# Supply_Modulator.net
KiCad netlist of a schematic drawn in Altium Designer
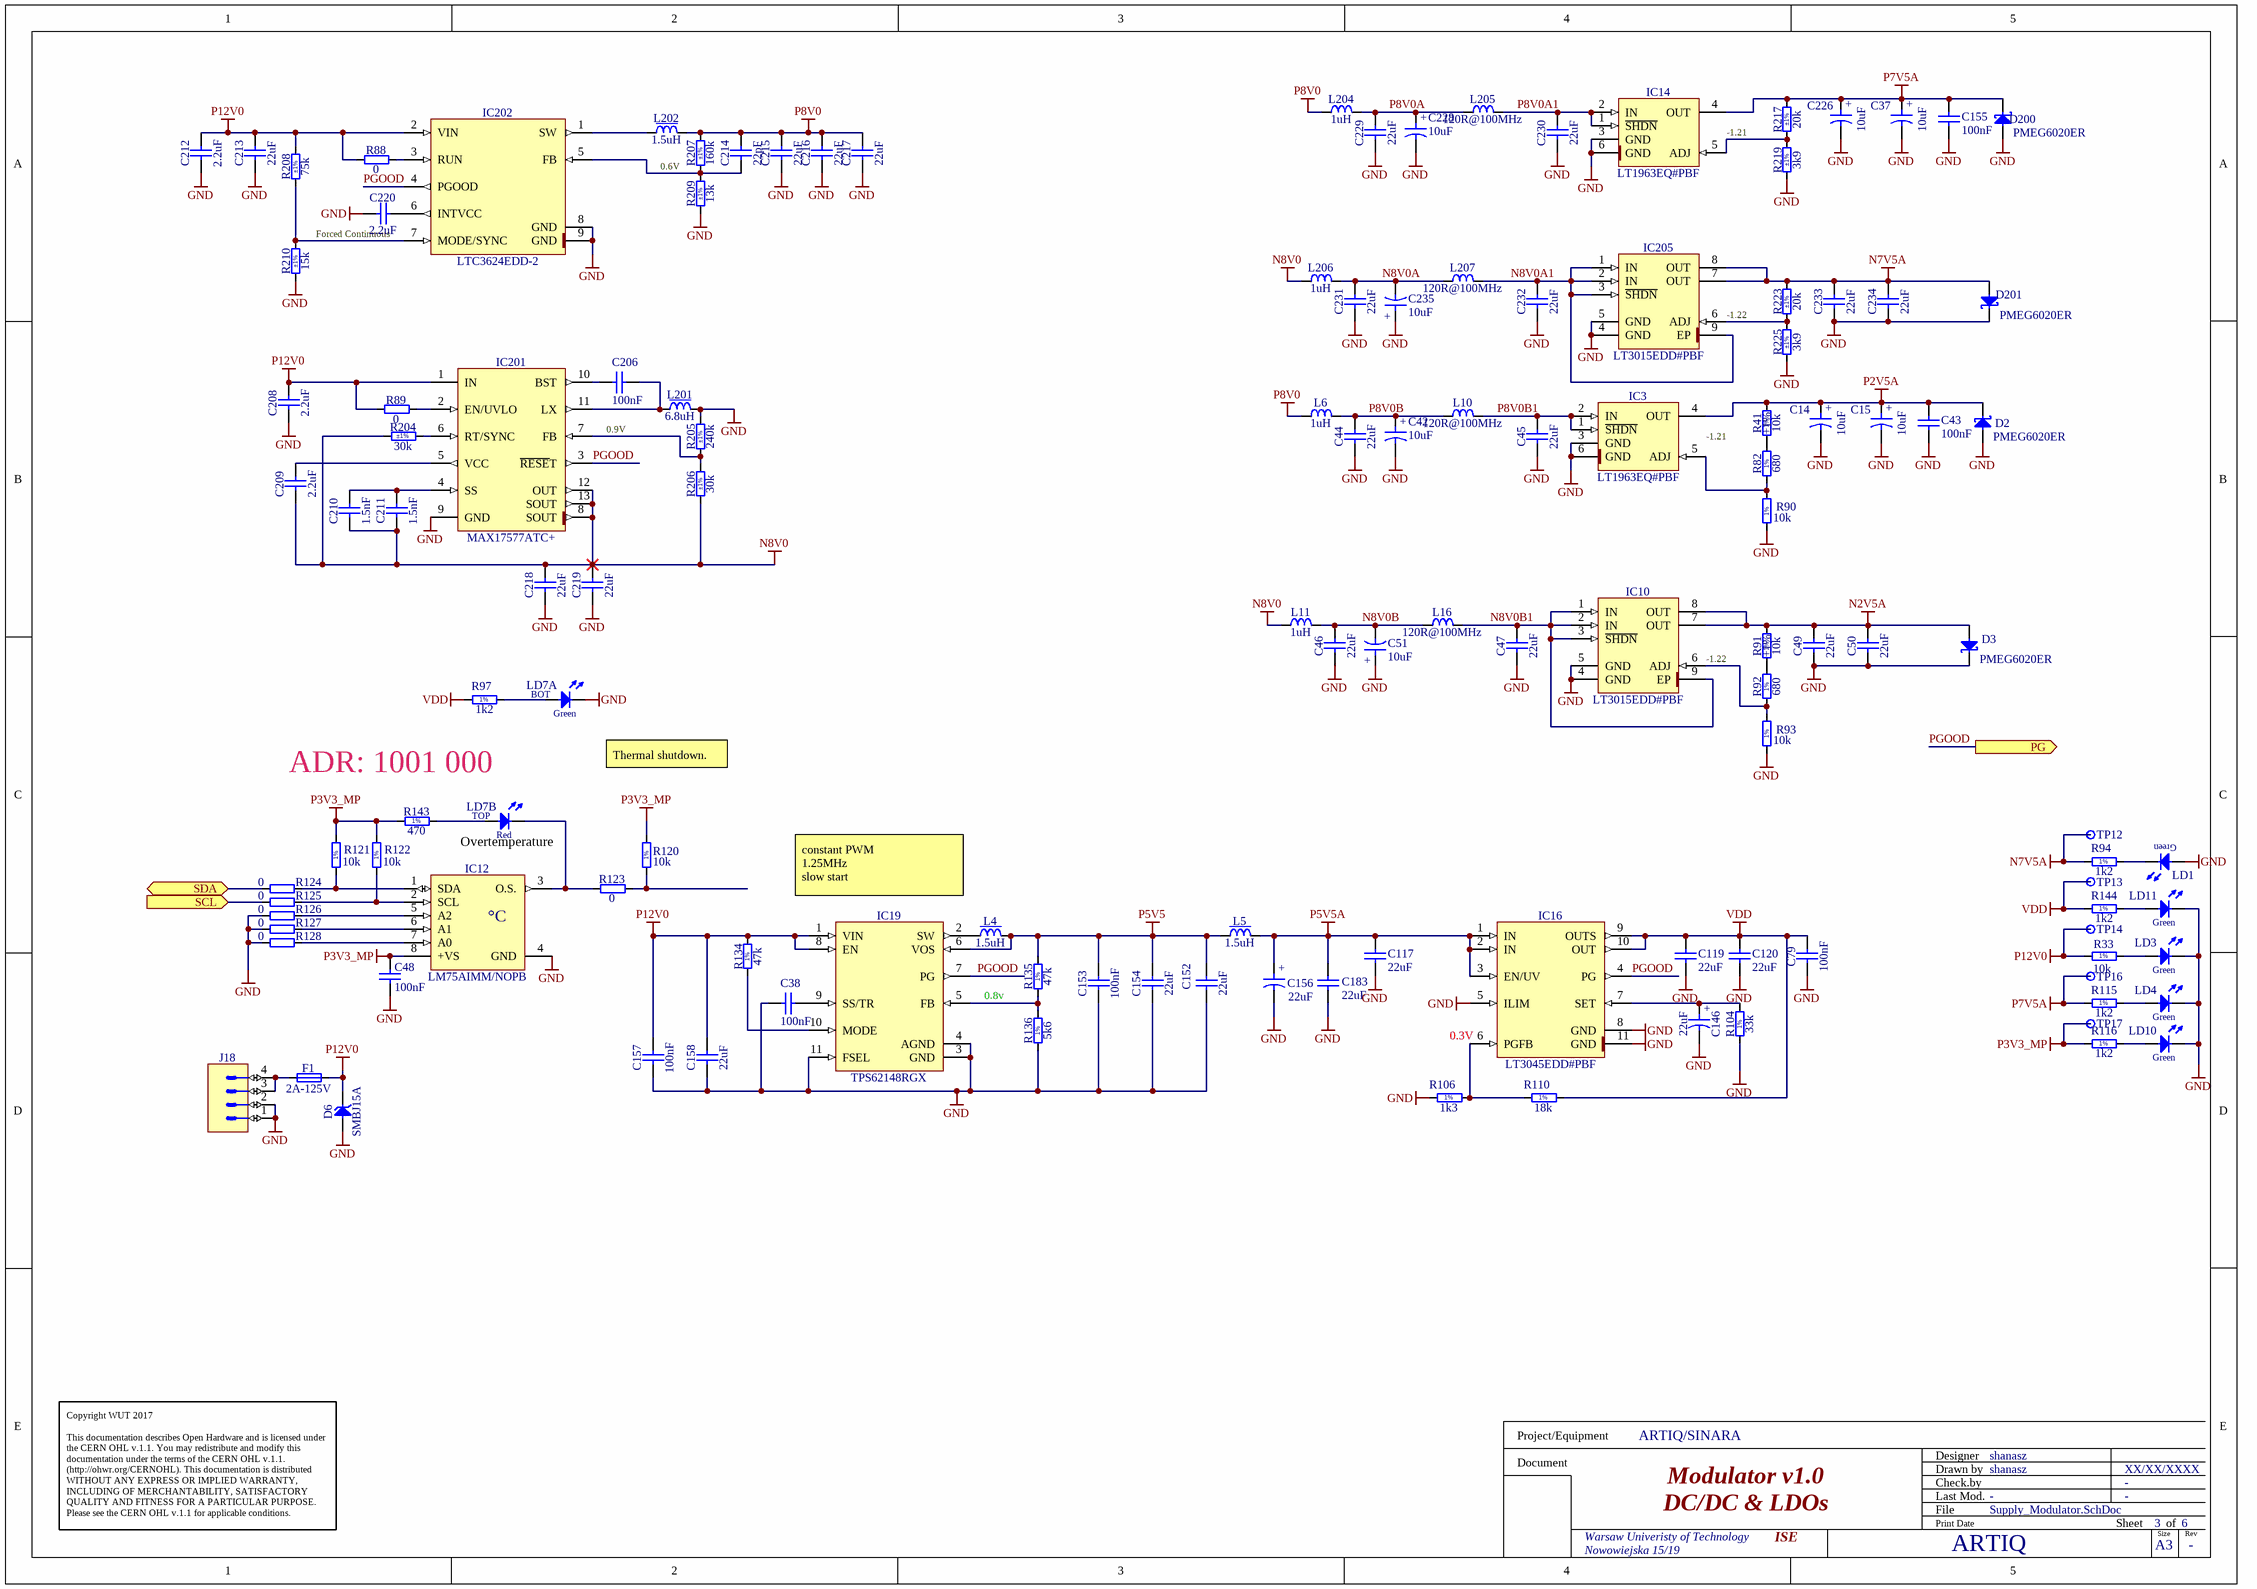
[diagram p0: Supply_Modulator.SchDoc]

(export (version "E")
  (design (tool "Eeschema 10.0.6"))
  (components
    (comp (ref "C14")
      (value "10uF")
      (footprint "CAPMP3216X180N")
      (description "Polarised capacitor")
      (fields
        (field (name "PART NUMBER") "CTE3216-18_10UF_16V_20%_AVX_TCJ")
        (field (name "VOLTAGE") "16V")
        (field (name "AUTHOR") "CERN DEM JLC")
      )
      (libsource (lib "Capacitors") (part "Capacitor - polarized"))
    )
    (comp (ref "C15")
      (value "10uF")
      (footprint "CAPMP3216X180N")
      (description "Polarised capacitor")
      (fields
        (field (name "PART NUMBER") "CTE3216-18_10UF_16V_20%_AVX_TCJ")
        (field (name "VOLTAGE") "16V")
        (field (name "AUTHOR") "CERN DEM JLC")
      )
      (libsource (lib "Capacitors") (part "Capacitor - polarized"))
    )
    (comp (ref "C37")
      (value "10uF")
      (footprint "CAPMP3216X180N")
      (description "Polarised capacitor")
      (fields
        (field (name "PART NUMBER") "CTE3216-18_10UF_16V_20%_AVX_TCJ")
        (field (name "VOLTAGE") "16V")
        (field (name "AUTHOR") "CERN DEM JLC")
      )
      (libsource (lib "Capacitors") (part "Capacitor - polarized"))
    )
    (comp (ref "C38")
      (value "100nF")
      (footprint "CAPC1005X55N")
      (description "Non-polarised capacitor")
      (fields
        (field (name "PART NUMBER") "CC0402_100NF_16V_10%_X5R")
        (field (name "VOLTAGE") "16V")
        (field (name "AUTHOR") "CERN DEM JLC")
      )
      (libsource (lib "Capacitors") (part "Capacitor - non polarized"))
    )
    (comp (ref "C42")
      (value "10uF")
      (footprint "CAPMP3216X180N")
      (description "Polarised capacitor")
      (fields
        (field (name "PART NUMBER") "CTE3216-18_10UF_16V_20%_AVX_TCJ")
        (field (name "VOLTAGE") "16V")
        (field (name "AUTHOR") "CERN DEM JLC")
      )
      (libsource (lib "Capacitors") (part "Capacitor - polarized"))
    )
    (comp (ref "C43")
      (value "100nF")
      (footprint "CAPC1005X55N")
      (description "Non-polarised capacitor")
      (fields
        (field (name "PART NUMBER") "CC0402_100NF_16V_10%_X5R")
        (field (name "VOLTAGE") "16V")
        (field (name "AUTHOR") "CERN DEM JLC")
      )
      (libsource (lib "Capacitors") (part "Capacitor - non polarized"))
    )
    (comp (ref "C44")
      (value "22uF")
      (footprint "CAPC2012X135N")
      (description "Non-polarised capacitor")
      (fields
        (field (name "PART NUMBER") "CC0805_22UF_16V_10%_X5R")
        (field (name "VOLTAGE") "16V")
        (field (name "AUTHOR") "CERN DEM JLC")
      )
      (libsource (lib "Capacitors") (part "Capacitor - non polarized"))
    )
    (comp (ref "C45")
      (value "22uF")
      (footprint "CAPC2012X135N")
      (description "Non-polarised capacitor")
      (fields
        (field (name "PART NUMBER") "CC0805_22UF_16V_10%_X5R")
        (field (name "VOLTAGE") "16V")
        (field (name "AUTHOR") "CERN DEM JLC")
      )
      (libsource (lib "Capacitors") (part "Capacitor - non polarized"))
    )
    (comp (ref "C46")
      (value "22uF")
      (footprint "CAPC2012X135N")
      (description "Non-polarised capacitor")
      (fields
        (field (name "PART NUMBER") "CC0805_22UF_16V_10%_X5R")
        (field (name "VOLTAGE") "16V")
        (field (name "AUTHOR") "CERN DEM JLC")
      )
      (libsource (lib "Capacitors") (part "Capacitor - non polarized"))
    )
    (comp (ref "C47")
      (value "22uF")
      (footprint "CAPC2012X135N")
      (description "Non-polarised capacitor")
      (fields
        (field (name "PART NUMBER") "CC0805_22UF_16V_10%_X5R")
        (field (name "VOLTAGE") "16V")
        (field (name "AUTHOR") "CERN DEM JLC")
      )
      (libsource (lib "Capacitors") (part "Capacitor - non polarized"))
    )
    (comp (ref "C48")
      (value "100nF")
      (footprint "CAPC1005X55N")
      (description "Non-polarised capacitor")
      (fields
        (field (name "PART NUMBER") "CC0402_100NF_16V_10%_X5R")
        (field (name "VOLTAGE") "16V")
        (field (name "AUTHOR") "CERN DEM JLC")
      )
      (libsource (lib "Capacitors") (part "Capacitor - non polarized"))
    )
    (comp (ref "C49")
      (value "22uF")
      (footprint "CAPC2012X135N")
      (description "Non-polarised capacitor")
      (fields
        (field (name "PART NUMBER") "CC0805_22UF_16V_10%_X5R")
        (field (name "VOLTAGE") "16V")
        (field (name "AUTHOR") "CERN DEM JLC")
      )
      (libsource (lib "Capacitors") (part "Capacitor - non polarized"))
    )
    (comp (ref "C50")
      (value "22uF")
      (footprint "CAPC2012X135N")
      (description "Non-polarised capacitor")
      (fields
        (field (name "PART NUMBER") "CC0805_22UF_16V_10%_X5R")
        (field (name "VOLTAGE") "16V")
        (field (name "AUTHOR") "CERN DEM JLC")
      )
      (libsource (lib "Capacitors") (part "Capacitor - non polarized"))
    )
    (comp (ref "C51")
      (value "10uF")
      (footprint "CAPMP3216X180N")
      (description "Polarised capacitor")
      (fields
        (field (name "PART NUMBER") "CTE3216-18_10UF_16V_20%_AVX_TCJ")
        (field (name "VOLTAGE") "16V")
        (field (name "AUTHOR") "CERN DEM JLC")
      )
      (libsource (lib "Capacitors") (part "Capacitor - polarized"))
    )
    (comp (ref "C79")
      (value "100nF")
      (footprint "CAPC1005X55N")
      (description "Non-polarised capacitor")
      (fields
        (field (name "PART NUMBER") "CC0402_100NF_16V_10%_X5R")
        (field (name "VOLTAGE") "16V")
        (field (name "AUTHOR") "CERN DEM JLC")
      )
      (libsource (lib "Capacitors") (part "Capacitor - non polarized"))
    )
    (comp (ref "C117")
      (value "22uF")
      (footprint "CAPC2012X135N")
      (description "Non-polarised capacitor")
      (fields
        (field (name "PART NUMBER") "CC0805_22UF_16V_10%_X5R")
        (field (name "VOLTAGE") "16V")
        (field (name "AUTHOR") "CERN DEM JLC")
      )
      (libsource (lib "Capacitors") (part "Capacitor - non polarized"))
    )
    (comp (ref "C119")
      (value "22uF")
      (footprint "CAPC2012X135N")
      (description "Non-polarised capacitor")
      (fields
        (field (name "PART NUMBER") "CC0805_22UF_16V_10%_X5R")
        (field (name "VOLTAGE") "16V")
        (field (name "AUTHOR") "CERN DEM JLC")
      )
      (libsource (lib "Capacitors") (part "Capacitor - non polarized"))
    )
    (comp (ref "C120")
      (value "22uF")
      (footprint "CAPC2012X135N")
      (description "Non-polarised capacitor")
      (fields
        (field (name "PART NUMBER") "CC0805_22UF_16V_10%_X5R")
        (field (name "VOLTAGE") "16V")
        (field (name "AUTHOR") "CERN DEM JLC")
      )
      (libsource (lib "Capacitors") (part "Capacitor - non polarized"))
    )
    (comp (ref "C146")
      (value "22uF")
      (footprint "CAPMP3528X210N")
      (description "Polarised capacitor")
      (fields
        (field (name "PART NUMBER") "CTE3528-21_22UF_10V_10%_LESR0700")
        (field (name "VOLTAGE") "10V")
        (field (name "AUTHOR") "CERN DEM JLC")
      )
      (libsource (lib "Capacitors") (part "Capacitor - polarized"))
    )
    (comp (ref "C152")
      (value "22uF")
      (footprint "CAPC2012X135N")
      (description "Non-polarised capacitor")
      (fields
        (field (name "PART NUMBER") "CC0805_22UF_16V_10%_X5R")
        (field (name "VOLTAGE") "16V")
        (field (name "AUTHOR") "CERN DEM JLC")
      )
      (libsource (lib "Capacitors") (part "Capacitor - non polarized"))
    )
    (comp (ref "C153")
      (value "100nF")
      (footprint "CAPC1005X55N")
      (description "Non-polarised capacitor")
      (fields
        (field (name "PART NUMBER") "CC0402_100NF_16V_10%_X5R")
        (field (name "VOLTAGE") "16V")
        (field (name "AUTHOR") "CERN DEM JLC")
      )
      (libsource (lib "Capacitors") (part "Capacitor - non polarized"))
    )
    (comp (ref "C154")
      (value "22uF")
      (footprint "CAPC2012X135N")
      (description "Non-polarised capacitor")
      (fields
        (field (name "PART NUMBER") "CC0805_22UF_16V_10%_X5R")
        (field (name "VOLTAGE") "16V")
        (field (name "AUTHOR") "CERN DEM JLC")
      )
      (libsource (lib "Capacitors") (part "Capacitor - non polarized"))
    )
    (comp (ref "C155")
      (value "100nF")
      (footprint "CAPC1005X55N")
      (description "Non-polarised capacitor")
      (fields
        (field (name "PART NUMBER") "CC0402_100NF_16V_10%_X5R")
        (field (name "VOLTAGE") "16V")
        (field (name "AUTHOR") "CERN DEM JLC")
      )
      (libsource (lib "Capacitors") (part "Capacitor - non polarized"))
    )
    (comp (ref "C156")
      (value "22uF")
      (footprint "CAPMP3528X210N")
      (description "Polarised capacitor")
      (fields
        (field (name "PART NUMBER") "CTE3528-21_22UF_10V_10%_LESR0700")
        (field (name "VOLTAGE") "10V")
        (field (name "AUTHOR") "CERN DEM JLC")
      )
      (libsource (lib "Capacitors") (part "Capacitor - polarized"))
    )
    (comp (ref "C157")
      (value "100nF")
      (footprint "CAPC1005X55N")
      (description "Non-polarised capacitor")
      (fields
        (field (name "PART NUMBER") "CC0402_100NF_16V_10%_X5R")
        (field (name "VOLTAGE") "16V")
        (field (name "AUTHOR") "CERN DEM JLC")
      )
      (libsource (lib "Capacitors") (part "Capacitor - non polarized"))
    )
    (comp (ref "C158")
      (value "22uF")
      (footprint "CAPC2012X135N")
      (description "Non-polarised capacitor")
      (fields
        (field (name "PART NUMBER") "CC0805_22UF_16V_10%_X5R")
        (field (name "VOLTAGE") "16V")
        (field (name "AUTHOR") "CERN DEM JLC")
      )
      (libsource (lib "Capacitors") (part "Capacitor - non polarized"))
    )
    (comp (ref "C183")
      (value "22uF")
      (footprint "CAPC2012X135N")
      (description "Non-polarised capacitor")
      (fields
        (field (name "PART NUMBER") "CC0805_22UF_16V_10%_X5R")
        (field (name "VOLTAGE") "16V")
        (field (name "AUTHOR") "CERN DEM JLC")
      )
      (libsource (lib "Capacitors") (part "Capacitor - non polarized"))
    )
    (comp (ref "C206")
      (value "100nF")
      (footprint "CAPC1005X55N")
      (description "Non-polarised capacitor")
      (fields
        (field (name "PART NUMBER") "CC0402_100NF_16V_10%_X5R")
        (field (name "VOLTAGE") "16V")
        (field (name "AUTHOR") "CERN DEM JLC")
      )
      (libsource (lib "Capacitors") (part "Capacitor - non polarized"))
    )
    (comp (ref "C208")
      (value "2.2uF")
      (footprint "CAPC1608X87N")
      (description "Non-polarised capacitor")
      (fields
        (field (name "PART NUMBER") "CC0603_2.2UF_16V_10%_X5R")
        (field (name "VOLTAGE") "16V")
        (field (name "AUTHOR") "CERN DEM JLC")
      )
      (libsource (lib "Capacitors") (part "Capacitor - non polarized"))
    )
    (comp (ref "C209")
      (value "2.2uF")
      (footprint "CAPC1608X87N")
      (description "Non-polarised capacitor")
      (fields
        (field (name "PART NUMBER") "CC0603_2.2UF_16V_10%_X5R")
        (field (name "VOLTAGE") "16V")
        (field (name "AUTHOR") "CERN DEM JLC")
      )
      (libsource (lib "Capacitors") (part "Capacitor - non polarized"))
    )
    (comp (ref "C210")
      (value "1.5nF")
      (footprint "CAPC1005X55N")
      (description "Non-polarised capacitor")
      (fields
        (field (name "PART NUMBER") "CC0402_1.5NF_50V_5%_C0G")
        (field (name "VOLTAGE") "50V")
        (field (name "AUTHOR") "CERN DEM BC")
      )
      (libsource (lib "Capacitors") (part "Capacitor - non polarized"))
    )
    (comp (ref "C211")
      (value "1.5nF")
      (footprint "CAPC1005X55N")
      (description "Non-polarised capacitor")
      (fields
        (field (name "PART NUMBER") "CC0402_1.5NF_50V_5%_C0G")
        (field (name "VOLTAGE") "50V")
        (field (name "AUTHOR") "CERN DEM BC")
      )
      (libsource (lib "Capacitors") (part "Capacitor - non polarized"))
    )
    (comp (ref "C212")
      (value "2.2uF")
      (footprint "CAPC1608X87N")
      (description "Non-polarised capacitor")
      (fields
        (field (name "PART NUMBER") "CC0603_2.2UF_16V_10%_X5R")
        (field (name "VOLTAGE") "16V")
        (field (name "AUTHOR") "CERN DEM JLC")
      )
      (libsource (lib "Capacitors") (part "Capacitor - non polarized"))
    )
    (comp (ref "C213")
      (value "22uF")
      (footprint "CAPC2012X135N")
      (description "Non-polarised capacitor")
      (fields
        (field (name "PART NUMBER") "CC0805_22UF_16V_10%_X5R")
        (field (name "VOLTAGE") "16V")
        (field (name "AUTHOR") "CERN DEM JLC")
      )
      (libsource (lib "Capacitors") (part "Capacitor - non polarized"))
    )
    (comp (ref "C214")
      (value "22pF")
      (footprint "CAPC1608X87N")
      (description "Non-polarised capacitor")
      (fields
        (field (name "PART NUMBER") "CC0603_22PF_50V_5%_NP0")
        (field (name "VOLTAGE") "50V")
        (field (name "AUTHOR") "CERN DEM JLC")
      )
      (libsource (lib "Capacitors") (part "Capacitor - non polarized"))
    )
    (comp (ref "C215")
      (value "22uF")
      (footprint "CAPC2012X135N")
      (description "Non-polarised capacitor")
      (fields
        (field (name "PART NUMBER") "CC0805_22UF_16V_10%_X5R")
        (field (name "VOLTAGE") "16V")
        (field (name "AUTHOR") "CERN DEM JLC")
      )
      (libsource (lib "Capacitors") (part "Capacitor - non polarized"))
    )
    (comp (ref "C216")
      (value "22uF")
      (footprint "CAPC2012X135N")
      (description "Non-polarised capacitor")
      (fields
        (field (name "PART NUMBER") "CC0805_22UF_16V_10%_X5R")
        (field (name "VOLTAGE") "16V")
        (field (name "AUTHOR") "CERN DEM JLC")
      )
      (libsource (lib "Capacitors") (part "Capacitor - non polarized"))
    )
    (comp (ref "C217")
      (value "22uF")
      (footprint "CAPC2012X135N")
      (description "Non-polarised capacitor")
      (fields
        (field (name "PART NUMBER") "CC0805_22UF_16V_10%_X5R")
        (field (name "VOLTAGE") "16V")
        (field (name "AUTHOR") "CERN DEM JLC")
      )
      (libsource (lib "Capacitors") (part "Capacitor - non polarized"))
    )
    (comp (ref "C218")
      (value "22uF")
      (footprint "CAPC2012X135N")
      (description "Non-polarised capacitor")
      (fields
        (field (name "PART NUMBER") "CC0805_22UF_16V_10%_X5R")
        (field (name "VOLTAGE") "16V")
        (field (name "AUTHOR") "CERN DEM JLC")
      )
      (libsource (lib "Capacitors") (part "Capacitor - non polarized"))
    )
    (comp (ref "C219")
      (value "22uF")
      (footprint "CAPC2012X135N")
      (description "Non-polarised capacitor")
      (fields
        (field (name "PART NUMBER") "CC0805_22UF_16V_10%_X5R")
        (field (name "VOLTAGE") "16V")
        (field (name "AUTHOR") "CERN DEM JLC")
      )
      (libsource (lib "Capacitors") (part "Capacitor - non polarized"))
    )
    (comp (ref "C220")
      (value "2.2uF")
      (footprint "CAPC1608X87N")
      (description "Non-polarised capacitor")
      (fields
        (field (name "PART NUMBER") "CC0603_2.2UF_16V_10%_X5R")
        (field (name "VOLTAGE") "16V")
        (field (name "AUTHOR") "CERN DEM JLC")
      )
      (libsource (lib "Capacitors") (part "Capacitor - non polarized"))
    )
    (comp (ref "C226")
      (value "10uF")
      (footprint "CAPMP3216X180N")
      (description "Polarised capacitor")
      (fields
        (field (name "PART NUMBER") "CTE3216-18_10UF_16V_20%_AVX_TCJ")
        (field (name "VOLTAGE") "16V")
        (field (name "AUTHOR") "CERN DEM JLC")
      )
      (libsource (lib "Capacitors") (part "Capacitor - polarized"))
    )
    (comp (ref "C228")
      (value "10uF")
      (footprint "CAPMP3216X180N")
      (description "Polarised capacitor")
      (fields
        (field (name "PART NUMBER") "CTE3216-18_10UF_16V_20%_AVX_TCJ")
        (field (name "VOLTAGE") "16V")
        (field (name "AUTHOR") "CERN DEM JLC")
      )
      (libsource (lib "Capacitors") (part "Capacitor - polarized"))
    )
    (comp (ref "C229")
      (value "22uF")
      (footprint "CAPC2012X135N")
      (description "Non-polarised capacitor")
      (fields
        (field (name "PART NUMBER") "CC0805_22UF_16V_10%_X5R")
        (field (name "VOLTAGE") "16V")
        (field (name "AUTHOR") "CERN DEM JLC")
      )
      (libsource (lib "Capacitors") (part "Capacitor - non polarized"))
    )
    (comp (ref "C230")
      (value "22uF")
      (footprint "CAPC2012X135N")
      (description "Non-polarised capacitor")
      (fields
        (field (name "PART NUMBER") "CC0805_22UF_16V_10%_X5R")
        (field (name "VOLTAGE") "16V")
        (field (name "AUTHOR") "CERN DEM JLC")
      )
      (libsource (lib "Capacitors") (part "Capacitor - non polarized"))
    )
    (comp (ref "C231")
      (value "22uF")
      (footprint "CAPC2012X135N")
      (description "Non-polarised capacitor")
      (fields
        (field (name "PART NUMBER") "CC0805_22UF_16V_10%_X5R")
        (field (name "VOLTAGE") "16V")
        (field (name "AUTHOR") "CERN DEM JLC")
      )
      (libsource (lib "Capacitors") (part "Capacitor - non polarized"))
    )
    (comp (ref "C232")
      (value "22uF")
      (footprint "CAPC2012X135N")
      (description "Non-polarised capacitor")
      (fields
        (field (name "PART NUMBER") "CC0805_22UF_16V_10%_X5R")
        (field (name "VOLTAGE") "16V")
        (field (name "AUTHOR") "CERN DEM JLC")
      )
      (libsource (lib "Capacitors") (part "Capacitor - non polarized"))
    )
    (comp (ref "C233")
      (value "22uF")
      (footprint "CAPC2012X135N")
      (description "Non-polarised capacitor")
      (fields
        (field (name "PART NUMBER") "CC0805_22UF_16V_10%_X5R")
        (field (name "VOLTAGE") "16V")
        (field (name "AUTHOR") "CERN DEM JLC")
      )
      (libsource (lib "Capacitors") (part "Capacitor - non polarized"))
    )
    (comp (ref "C234")
      (value "22uF")
      (footprint "CAPC2012X135N")
      (description "Non-polarised capacitor")
      (fields
        (field (name "PART NUMBER") "CC0805_22UF_16V_10%_X5R")
        (field (name "VOLTAGE") "16V")
        (field (name "AUTHOR") "CERN DEM JLC")
      )
      (libsource (lib "Capacitors") (part "Capacitor - non polarized"))
    )
    (comp (ref "C235")
      (value "10uF")
      (footprint "CAPMP3216X180N")
      (description "Polarised capacitor")
      (fields
        (field (name "PART NUMBER") "CTE3216-18_10UF_16V_20%_AVX_TCJ")
        (field (name "VOLTAGE") "16V")
        (field (name "AUTHOR") "CERN DEM JLC")
      )
      (libsource (lib "Capacitors") (part "Capacitor - polarized"))
    )
    (comp (ref "D2")
      (value "PMEG6020ER")
      (footprint "SODFL3517X110N")
      (description "Schottky Diode")
      (fields
        (field (name "VOLTAGE") "60V")
        (field (name "POWER") "2A")
        (field (name "AUTHOR") "CERN DEM JMW")
      )
      (libsource (lib "ICs And Semiconductors") (part "Diode Schottky"))
    )
    (comp (ref "D3")
      (value "PMEG6020ER")
      (footprint "SODFL3517X110N")
      (description "Schottky Diode")
      (fields
        (field (name "VOLTAGE") "60V")
        (field (name "POWER") "2A")
        (field (name "AUTHOR") "CERN DEM JMW")
      )
      (libsource (lib "ICs And Semiconductors") (part "Diode Schottky"))
    )
    (comp (ref "D6")
      (value "SMBJ15A")
      (footprint "DIOM5336X265N")
      (description "Zener Diode")
      (fields
        (field (name "VOLTAGE") "15V")
        (field (name "POWER") "600W")
        (field (name "AUTHOR") "CERN DEM JLC")
      )
      (libsource (lib "ICs And Semiconductors") (part "Diode Zener"))
    )
    (comp (ref "D200")
      (value "PMEG6020ER")
      (footprint "SODFL3517X110N")
      (description "Schottky Diode")
      (fields
        (field (name "VOLTAGE") "60V")
        (field (name "POWER") "2A")
        (field (name "AUTHOR") "CERN DEM JMW")
      )
      (libsource (lib "ICs And Semiconductors") (part "Diode Schottky"))
    )
    (comp (ref "D201")
      (value "PMEG6020ER")
      (footprint "SODFL3517X110N")
      (description "Schottky Diode")
      (fields
        (field (name "VOLTAGE") "60V")
        (field (name "POWER") "2A")
        (field (name "AUTHOR") "CERN DEM JMW")
      )
      (libsource (lib "ICs And Semiconductors") (part "Diode Schottky"))
    )
    (comp (ref "F1")
      (value "2A-125V")
      (footprint "FUSE_LITTELFUSE_0154")
      (description "Fuse")
      (fields
        (field (name "PART NUMBER") "FUSE_LITTELFUSE_0154002.DRT")
        (field (name "MANUFACTURER") "LITTELFUSE")
        (field (name "AUTHOR") "CERN DEM JLC")
      )
      (libsource (lib "Eletro-mechanical") (part "Fuse"))
    )
    (comp (ref "IC3")
      (value "LT1963EQ#PBF")
      (footprint "TO170P1394X457-6N-R900X1060")
      (description "1.5A, Fast Transient Response Adjustable LDO Regulators")
      (fields (field (name "MANUFACTURER") "LINEAR TECHNOLOGY") (field (name "AUTHOR") "CERN DEM JLC"))
      (libsource (lib "ICs And Semiconductors") (part "LT1963xQ"))
    )
    (comp (ref "IC10")
      (value "LT3015EDD#PBF")
      (footprint "SON50P300X300X80-9N-R175X248")
      (description "1.5A, Low Noise, Negative Linear Regulator with Precision Current Limit")
      (fields (field (name "MANUFACTURER") "LINEAR TECHNOLOGY") (field (name "AUTHOR") "CERN DEM MR"))
      (libsource (lib "ICs And Semiconductors") (part "LT3015EDD"))
    )
    (comp (ref "IC12")
      (value "LM75AIMM/NOPB")
      (footprint "SOP65P490X109-8N")
      (description "Digital Temperature Sensor and Thermal Watchdog with Two-Wire Interface")
      (fields (field (name "MANUFACTURER") "TEXAS INSTRUMENTS") (field (name "AUTHOR") "CERN DEM JLC"))
      (libsource (lib "ICs And Semiconductors") (part "LM75"))
    )
    (comp (ref "IC14")
      (value "LT1963EQ#PBF")
      (footprint "TO170P1394X457-6N-R900X1060")
      (description "1.5A, Fast Transient Response Adjustable LDO Regulators")
      (fields (field (name "MANUFACTURER") "LINEAR TECHNOLOGY") (field (name "AUTHOR") "CERN DEM JLC"))
      (libsource (lib "ICs And Semiconductors") (part "LT1963xQ"))
    )
    (comp (ref "IC16")
      (value "LT3045EDD#PBF")
      (footprint "SON50P300X300X80-11N-R175X248")
      (description "20V, 500mA, Ultralow Noise, Ultrahigh PSRR Linear Regulator")
      (fields (field (name "MANUFACTURER") "LINEAR TECHNOLOGY") (field (name "AUTHOR") "CERN DEM JLC"))
      (libsource (lib "ICs And Semiconductors") (part "LT3045EDD"))
    )
    (comp (ref "IC19")
      (value "TPS62148RGX")
      (footprint "TEXAS_RGX0011A")
      (description "3V-17V 2A Step-Down Converter, High Accuracy, With DCS-Control")
      (fields (field (name "MANUFACTURER") "TEXAS INSTRUMENTS") (field (name "AUTHOR") "CERN DEM MR"))
      (libsource (lib "ICs And Semiconductors") (part "TPS62148"))
    )
    (comp (ref "IC201")
      (value "MAX17577ATC+")
      (footprint "SON50P300X300X80-13N-R180X260")
      (description "4.5V to 60V, 1A High-Efficiency, Synchronous, Inverting Output DC-DC Converters")
      (fields (field (name "MANUFACTURER") "MAXIM") (field (name "AUTHOR") "CERN DEM HF"))
      (libsource (lib "Modulator_pLib") (part "MAX17577"))
    )
    (comp (ref "IC202")
      (value "LTC3624EDD-2")
      (footprint "SON50P300X300X80-9N-R175X248")
      (description "Adjustable, 2A, Synchronous Step-Down Regulator with 3.5µA Quiescent Current")
      (fields (field (name "MANUFACTURER") "LINEAR TECHNOLOGY") (field (name "AUTHOR") "CERN DEM HF"))
      (libsource (lib "Modulator_pLib") (part "LTC3624 _DD"))
    )
    (comp (ref "IC205")
      (value "LT3015EDD#PBF")
      (footprint "SON50P300X300X80-9N-R175X248")
      (description "1.5A, Low Noise, Negative Linear Regulator with Precision Current Limit")
      (fields (field (name "MANUFACTURER") "LINEAR TECHNOLOGY") (field (name "AUTHOR") "CERN DEM MR"))
      (libsource (lib "ICs And Semiconductors") (part "LT3015EDD"))
    )
    (comp (ref "J18")
      (value "Mini-Fit Jr.™")
      (footprint "MOLEX_39-30-0040")
      (description "Connector 4 Male")
      (fields
        (field (name "PART NUMBER") "MOLEX_39-30-0040")
        (field (name "MANUFACTURER") "MOLEX")
        (field (name "AUTHOR") "CERN DEM JLC")
      )
      (libsource (lib "Connectors") (part "Connector 4 Male"))
    )
    (comp (ref "L4")
      (value "1.5uH")
      (footprint "IND_TDK_SPM6530")
      (description "Inductor With Core")
      (fields
        (field (name "PART NUMBER") "IND_1.5UH_20%_TDK_SPM6530")
        (field (name "POWER") "11A")
        (field (name "AUTHOR") "CERN DEM MR")
      )
      (libsource (lib "Inductors & Transformers") (part "Inductor With Magnetic core"))
    )
    (comp (ref "L5")
      (value "1.5uH")
      (footprint "IND_TDK_SPM6530")
      (description "Inductor With Core")
      (fields
        (field (name "PART NUMBER") "IND_1.5UH_20%_TDK_SPM6530")
        (field (name "POWER") "11A")
        (field (name "AUTHOR") "CERN DEM MR")
      )
      (libsource (lib "Inductors & Transformers") (part "Inductor With Magnetic core"))
    )
    (comp (ref "L6")
      (value "1uH")
      (footprint "INDC2620X100N")
      (description "Inductor")
      (fields
        (field (name "PART NUMBER") "IND1008_1UH_20%_WURTH_74479787210B")
        (field (name "POWER") "1.95A")
        (field (name "AUTHOR") "CERN DEM JLC")
      )
      (libsource (lib "Inductors & Transformers") (part "Inductor"))
    )
    (comp (ref "L10")
      (value "120R@100MHz")
      (footprint "INDC1608X65N")
      (description "Inductor")
      (fields
        (field (name "PART NUMBER") "IND0603_MURATA_BLM18SG121TN1D")
        (field (name "POWER") "3A")
        (field (name "AUTHOR") "CERN DEM JLC")
      )
      (libsource (lib "Inductors & Transformers") (part "Inductor"))
    )
    (comp (ref "L11")
      (value "1uH")
      (footprint "INDC2620X100N")
      (description "Inductor")
      (fields
        (field (name "PART NUMBER") "IND1008_1UH_20%_WURTH_74479787210B")
        (field (name "POWER") "1.95A")
        (field (name "AUTHOR") "CERN DEM JLC")
      )
      (libsource (lib "Inductors & Transformers") (part "Inductor"))
    )
    (comp (ref "L16")
      (value "120R@100MHz")
      (footprint "INDC1608X65N")
      (description "Inductor")
      (fields
        (field (name "PART NUMBER") "IND0603_MURATA_BLM18SG121TN1D")
        (field (name "POWER") "3A")
        (field (name "AUTHOR") "CERN DEM JLC")
      )
      (libsource (lib "Inductors & Transformers") (part "Inductor"))
    )
    (comp (ref "L201")
      (value "6.8uH")
      (footprint "INDM6965X300N")
      (description "Inductor With Core")
      (fields
        (field (name "PART NUMBER") "IND2525_6.8UH_20%_VISHAY_IHLP-2525CZ-01")
        (field (name "POWER") "4.5A")
        (field (name "AUTHOR") "CERN DEM MR")
      )
      (libsource (lib "Inductors & Transformers") (part "Inductor With Magnetic core"))
    )
    (comp (ref "L202")
      (value "1.5uH")
      (footprint "INDM6965X300N")
      (description "Inductor With Core")
      (fields
        (field (name "PART NUMBER") "IND2525_1.5UH_20%_VISHAY_IHLP-2525CZ")
        (field (name "POWER") "9A")
        (field (name "AUTHOR") "CERN DEM JLC")
      )
      (libsource (lib "Inductors & Transformers") (part "Inductor With Magnetic core"))
    )
    (comp (ref "L204")
      (value "1uH")
      (footprint "INDC2620X100N")
      (description "Inductor")
      (fields
        (field (name "PART NUMBER") "IND1008_1UH_20%_WURTH_74479787210B")
        (field (name "POWER") "1.95A")
        (field (name "AUTHOR") "CERN DEM JLC")
      )
      (libsource (lib "Inductors & Transformers") (part "Inductor"))
    )
    (comp (ref "L205")
      (value "120R@100MHz")
      (footprint "INDC1608X65N")
      (description "Inductor")
      (fields
        (field (name "PART NUMBER") "IND0603_MURATA_BLM18SG121TN1D")
        (field (name "POWER") "3A")
        (field (name "AUTHOR") "CERN DEM JLC")
      )
      (libsource (lib "Inductors & Transformers") (part "Inductor"))
    )
    (comp (ref "L206")
      (value "1uH")
      (footprint "INDC2620X100N")
      (description "Inductor")
      (fields
        (field (name "PART NUMBER") "IND1008_1UH_20%_WURTH_74479787210B")
        (field (name "POWER") "1.95A")
        (field (name "AUTHOR") "CERN DEM JLC")
      )
      (libsource (lib "Inductors & Transformers") (part "Inductor"))
    )
    (comp (ref "L207")
      (value "120R@100MHz")
      (footprint "INDC1608X65N")
      (description "Inductor")
      (fields
        (field (name "PART NUMBER") "IND0603_MURATA_BLM18SG121TN1D")
        (field (name "POWER") "3A")
        (field (name "AUTHOR") "CERN DEM JLC")
      )
      (libsource (lib "Inductors & Transformers") (part "Inductor"))
    )
    (comp (ref "LD1")
      (value "Green")
      (footprint "LED_KINGBRIGHT_KPH-1608CGCKr")
      (description "Green 0603")
      (fields
        (field (name "PART NUMBER") "LED_KINGBRIGHT_KPH-1608CGCK")
        (field (name "MANUFACTURER") "KINGBRIGHT")
        (field (name "AUTHOR") "CERN DEM JLC")
      )
      (libsource (lib "LIBRARY_SCH") (part "LED_0603_Green"))
    )
    (comp (ref "LD3")
      (value "Green")
      (footprint "LED_KINGBRIGHT_KPH-1608CGCKr")
      (description "Green 0603")
      (fields
        (field (name "PART NUMBER") "LED_KINGBRIGHT_KPH-1608CGCK")
        (field (name "MANUFACTURER") "KINGBRIGHT")
        (field (name "AUTHOR") "CERN DEM JLC")
      )
      (libsource (lib "LIBRARY_SCH") (part "LED_0603_Green"))
    )
    (comp (ref "LD4")
      (value "Green")
      (footprint "LED_KINGBRIGHT_KPH-1608CGCKr")
      (description "Green 0603")
      (fields
        (field (name "PART NUMBER") "LED_KINGBRIGHT_KPH-1608CGCK")
        (field (name "MANUFACTURER") "KINGBRIGHT")
        (field (name "AUTHOR") "CERN DEM JLC")
      )
      (libsource (lib "LIBRARY_SCH") (part "LED_0603_Green"))
    )
    (comp (ref "LD7")
      (value "Red/Green")
      (footprint "LED_DIALIGHT_571-0112F")
      (description "2x LED  Botom Green, Top Red")
      (fields
        (field (name "PART NUMBER") "LED_DIALIGHT_571-0112F")
        (field (name "MANUFACTURER") "DIALIGHT")
        (field (name "AUTHOR") "CERN DEM JLC")
      )
      (libsource (lib "ICs And Semiconductors") (part "LED x2 G-1C2A-BOT_R-3C4A-TOP"))
    )
    (comp (ref "LD10")
      (value "Green")
      (footprint "LED_KINGBRIGHT_KPH-1608CGCKr")
      (description "Green 0603")
      (fields
        (field (name "PART NUMBER") "LED_KINGBRIGHT_KPH-1608CGCK")
        (field (name "MANUFACTURER") "KINGBRIGHT")
        (field (name "AUTHOR") "CERN DEM JLC")
      )
      (libsource (lib "LIBRARY_SCH") (part "LED_0603_Green"))
    )
    (comp (ref "LD11")
      (value "Green")
      (footprint "LED_KINGBRIGHT_KPH-1608CGCKr")
      (description "Green 0603")
      (fields
        (field (name "PART NUMBER") "LED_KINGBRIGHT_KPH-1608CGCK")
        (field (name "MANUFACTURER") "KINGBRIGHT")
        (field (name "AUTHOR") "CERN DEM JLC")
      )
      (libsource (lib "LIBRARY_SCH") (part "LED_0603_Green"))
    )
    (comp (ref "R33")
      (value "10k")
      (footprint "RESC1005X40N")
      (description "Resistor - 1%")
      (fields
        (field (name "PART NUMBER") "R0402_10K_1%_0.0625W_100PPM")
        (field (name "POWER") "0.0625W")
        (field (name "AUTHOR") "CERN DEM JLC")
      )
      (libsource (lib "Resistors") (part "Resistor - 1%"))
    )
    (comp (ref "R41")
      (value "10k")
      (footprint "RESC1005X40N")
      (description "Resistor - 1%")
      (fields
        (field (name "TOLERANCE") "±1%")
        (field (name "PART NUMBER") "R0402_10K_1%_0.0625W_100PPM")
        (field (name "POWER") "0.0625W")
        (field (name "AUTHOR") "CERN DEM JLC")
      )
      (libsource (lib "Resistors") (part "Resistor - 1%"))
    )
    (comp (ref "R82")
      (value "680")
      (footprint "RESC1005X40N")
      (description "Resistor - 1%")
      (fields
        (field (name "PART NUMBER") "R0402_680R_1%_0.0625W_100PPM")
        (field (name "MANUFACTURER") "GENERIC")
        (field (name "AUTHOR") "CERN DEM JLC")
      )
      (libsource (lib "Resistors") (part "Resistor - 1%"))
    )
    (comp (ref "R88")
      (value "0")
      (footprint "RESC1005X40N")
      (description "Resistor")
      (fields
        (field (name "PART NUMBER") "R0402_0R_JUMPER")
        (field (name "MANUFACTURER") "GENERIC")
        (field (name "AUTHOR") "CERN DEM JLC")
      )
      (libsource (lib "Resistors") (part "Resistor"))
    )
    (comp (ref "R89")
      (value "0")
      (footprint "RESC1005X40N")
      (description "Resistor")
      (fields
        (field (name "PART NUMBER") "R0402_0R_JUMPER")
        (field (name "MANUFACTURER") "GENERIC")
        (field (name "AUTHOR") "CERN DEM JLC")
      )
      (libsource (lib "Resistors") (part "Resistor"))
    )
    (comp (ref "R90")
      (value "10k")
      (footprint "RESC1005X40N")
      (description "Resistor - 1%")
      (fields
        (field (name "PART NUMBER") "R0402_10K_1%_0.0625W_100PPM")
        (field (name "POWER") "0.0625W")
        (field (name "AUTHOR") "CERN DEM JLC")
      )
      (libsource (lib "Resistors") (part "Resistor - 1%"))
    )
    (comp (ref "R91")
      (value "10k")
      (footprint "RESC1005X40N")
      (description "Resistor - 1%")
      (fields
        (field (name "TOLERANCE") "±1%")
        (field (name "PART NUMBER") "R0402_10K_1%_0.0625W_100PPM")
        (field (name "POWER") "0.0625W")
        (field (name "AUTHOR") "CERN DEM JLC")
      )
      (libsource (lib "Resistors") (part "Resistor - 1%"))
    )
    (comp (ref "R92")
      (value "680")
      (footprint "RESC1005X40N")
      (description "Resistor - 1%")
      (fields
        (field (name "PART NUMBER") "R0402_680R_1%_0.0625W_100PPM")
        (field (name "MANUFACTURER") "GENERIC")
        (field (name "AUTHOR") "CERN DEM JLC")
      )
      (libsource (lib "Resistors") (part "Resistor - 1%"))
    )
    (comp (ref "R93")
      (value "10k")
      (footprint "RESC1005X40N")
      (description "Resistor - 1%")
      (fields
        (field (name "PART NUMBER") "R0402_10K_1%_0.0625W_100PPM")
        (field (name "POWER") "0.0625W")
        (field (name "AUTHOR") "CERN DEM JLC")
      )
      (libsource (lib "Resistors") (part "Resistor - 1%"))
    )
    (comp (ref "R94")
      (value "1k2")
      (footprint "RESC1005X40N")
      (description "Resistor - 1%")
      (fields
        (field (name "PART NUMBER") "R0402_1K2_1%_0.0625W_100PPM")
        (field (name "POWER") "0.0625W")
        (field (name "AUTHOR") "CERN DEM JLC")
      )
      (libsource (lib "Resistors") (part "Resistor - 1%"))
    )
    (comp (ref "R97")
      (value "1k2")
      (footprint "RESC1005X40N")
      (description "Resistor - 1%")
      (fields
        (field (name "PART NUMBER") "R0402_1K2_1%_0.0625W_100PPM")
        (field (name "POWER") "0.0625W")
        (field (name "AUTHOR") "CERN DEM JLC")
      )
      (libsource (lib "Resistors") (part "Resistor - 1%"))
    )
    (comp (ref "R104")
      (value "33k")
      (footprint "RESC1005X40N")
      (description "Resistor - 1%")
      (fields
        (field (name "PART NUMBER") "R0402_33K_1%_0.0625W_100PPM")
        (field (name "POWER") "0.0625W")
        (field (name "AUTHOR") "CERN DEM JLC")
      )
      (libsource (lib "Resistors") (part "Resistor - 1%"))
    )
    (comp (ref "R106")
      (value "1k3")
      (footprint "RESC1608X55N")
      (description "Resistor - 1%")
      (fields
        (field (name "PART NUMBER") "R0603_1K3_1%_0.1W_100PPM")
        (field (name "POWER") "0.1W")
        (field (name "AUTHOR") "CERN DEM JLC")
      )
      (libsource (lib "") (part "Resistor - 1%_1"))
    )
    (comp (ref "R110")
      (value "18k")
      (footprint "RESC1005X40N")
      (description "Resistor - 1%")
      (fields
        (field (name "PART NUMBER") "R0402_18K_1%_0.0625W_100PPM")
        (field (name "POWER") "0.0625W")
        (field (name "AUTHOR") "CERN DEM JLC")
      )
      (libsource (lib "Resistors") (part "Resistor - 1%"))
    )
    (comp (ref "R115")
      (value "1k2")
      (footprint "RESC1005X40N")
      (description "Resistor - 1%")
      (fields
        (field (name "PART NUMBER") "R0402_1K2_1%_0.0625W_100PPM")
        (field (name "POWER") "0.0625W")
        (field (name "AUTHOR") "CERN DEM JLC")
      )
      (libsource (lib "Resistors") (part "Resistor - 1%"))
    )
    (comp (ref "R116")
      (value "1k2")
      (footprint "RESC1005X40N")
      (description "Resistor - 1%")
      (fields
        (field (name "PART NUMBER") "R0402_1K2_1%_0.0625W_100PPM")
        (field (name "POWER") "0.0625W")
        (field (name "AUTHOR") "CERN DEM JLC")
      )
      (libsource (lib "Resistors") (part "Resistor - 1%"))
    )
    (comp (ref "R120")
      (value "10k")
      (footprint "RESC1005X40N")
      (description "Resistor - 1%")
      (fields
        (field (name "PART NUMBER") "R0402_10K_1%_0.0625W_100PPM")
        (field (name "POWER") "0.0625W")
        (field (name "AUTHOR") "CERN DEM JLC")
      )
      (libsource (lib "Resistors") (part "Resistor - 1%"))
    )
    (comp (ref "R121")
      (value "10k")
      (footprint "RESC1005X40N")
      (description "Resistor - 1%")
      (fields
        (field (name "PART NUMBER") "R0402_10K_1%_0.0625W_100PPM")
        (field (name "POWER") "0.0625W")
        (field (name "AUTHOR") "CERN DEM JLC")
      )
      (libsource (lib "Resistors") (part "Resistor - 1%"))
    )
    (comp (ref "R122")
      (value "10k")
      (footprint "RESC1005X40N")
      (description "Resistor - 1%")
      (fields
        (field (name "PART NUMBER") "R0402_10K_1%_0.0625W_100PPM")
        (field (name "POWER") "0.0625W")
        (field (name "AUTHOR") "CERN DEM JLC")
      )
      (libsource (lib "Resistors") (part "Resistor - 1%"))
    )
    (comp (ref "R123")
      (value "0")
      (footprint "RESC1005X40N")
      (description "Resistor")
      (fields
        (field (name "PART NUMBER") "R0402_0R_JUMPER")
        (field (name "MANUFACTURER") "GENERIC")
        (field (name "AUTHOR") "CERN DEM JLC")
      )
      (libsource (lib "Resistors") (part "Resistor"))
    )
    (comp (ref "R124")
      (value "0")
      (footprint "RESC1005X40N")
      (description "Resistor")
      (fields
        (field (name "PART NUMBER") "R0402_0R_JUMPER")
        (field (name "MANUFACTURER") "GENERIC")
        (field (name "AUTHOR") "CERN DEM JLC")
      )
      (libsource (lib "Resistors") (part "Resistor"))
    )
    (comp (ref "R125")
      (value "0")
      (footprint "RESC1005X40N")
      (description "Resistor")
      (fields
        (field (name "PART NUMBER") "R0402_0R_JUMPER")
        (field (name "MANUFACTURER") "GENERIC")
        (field (name "AUTHOR") "CERN DEM JLC")
      )
      (libsource (lib "Resistors") (part "Resistor"))
    )
    (comp (ref "R126")
      (value "0")
      (footprint "RESC1005X40N")
      (description "Resistor")
      (fields
        (field (name "PART NUMBER") "R0402_0R_JUMPER")
        (field (name "MANUFACTURER") "GENERIC")
        (field (name "AUTHOR") "CERN DEM JLC")
      )
      (libsource (lib "Resistors") (part "Resistor"))
    )
    (comp (ref "R127")
      (value "0")
      (footprint "RESC1005X40N")
      (description "Resistor")
      (fields
        (field (name "PART NUMBER") "R0402_0R_JUMPER")
        (field (name "MANUFACTURER") "GENERIC")
        (field (name "AUTHOR") "CERN DEM JLC")
      )
      (libsource (lib "Resistors") (part "Resistor"))
    )
    (comp (ref "R128")
      (value "0")
      (footprint "RESC1005X40N")
      (description "Resistor")
      (fields
        (field (name "PART NUMBER") "R0402_0R_JUMPER")
        (field (name "MANUFACTURER") "GENERIC")
        (field (name "AUTHOR") "CERN DEM JLC")
      )
      (libsource (lib "Resistors") (part "Resistor"))
    )
    (comp (ref "R134")
      (value "47k")
      (footprint "RESC1005X40N")
      (description "Resistor - 1%")
      (fields
        (field (name "PART NUMBER") "R0402_47K_1%_0.0625W_100PPM")
        (field (name "POWER") "0.0625W")
        (field (name "AUTHOR") "CERN DEM JLC")
      )
      (libsource (lib "Resistors") (part "Resistor - 1%"))
    )
    (comp (ref "R135")
      (value "47k")
      (footprint "RESC1005X40N")
      (description "Resistor - 1%")
      (fields
        (field (name "PART NUMBER") "R0402_47K_1%_0.0625W_100PPM")
        (field (name "POWER") "0.0625W")
        (field (name "AUTHOR") "CERN DEM JLC")
      )
      (libsource (lib "Resistors") (part "Resistor - 1%"))
    )
    (comp (ref "R136")
      (value "5k6")
      (footprint "RESC1005X40N")
      (description "Resistor - 1%")
      (fields
        (field (name "PART NUMBER") "R0402_5K6_1%_0.0625W_100PPM")
        (field (name "POWER") "0.0625W")
        (field (name "AUTHOR") "CERN DEM JLC")
      )
      (libsource (lib "Resistors") (part "Resistor - 1%"))
    )
    (comp (ref "R143")
      (value "470")
      (footprint "RESC1005X40N")
      (description "Resistor - 1%")
      (fields
        (field (name "PART NUMBER") "R0402_470R_1%_0.0625W_100PPM")
        (field (name "POWER") "0.0625W")
        (field (name "AUTHOR") "CERN DEM JLC")
      )
      (libsource (lib "Resistors") (part "Resistor - 1%"))
    )
    (comp (ref "R144")
      (value "1k2")
      (footprint "RESC1005X40N")
      (description "Resistor - 1%")
      (fields
        (field (name "PART NUMBER") "R0402_1K2_1%_0.0625W_100PPM")
        (field (name "POWER") "0.0625W")
        (field (name "AUTHOR") "CERN DEM JLC")
      )
      (libsource (lib "Resistors") (part "Resistor - 1%"))
    )
    (comp (ref "R204")
      (value "30k")
      (footprint "RESC1005X40N")
      (description "Resistor - 1%")
      (fields
        (field (name "TOLERANCE") "±1%")
        (field (name "PART NUMBER") "R0402_30K_1%_0.0625W_100PPM")
        (field (name "POWER") "0.0625W")
        (field (name "AUTHOR") "CERN DEM JLC")
      )
      (libsource (lib "Resistors") (part "Resistor - 1%"))
    )
    (comp (ref "R205")
      (value "240k")
      (footprint "RESC1005X40N")
      (description "Resistor - 1%")
      (fields
        (field (name "TOLERANCE") "±1%")
        (field (name "PART NUMBER") "R0402_240K_1%_0.0625W_100PPM")
        (field (name "POWER") "0.0625W")
        (field (name "AUTHOR") "CERN DEM JLC")
      )
      (libsource (lib "Resistors") (part "Resistor - 1%"))
    )
    (comp (ref "R206")
      (value "30k")
      (footprint "RESC1005X40N")
      (description "Resistor - 1%")
      (fields
        (field (name "TOLERANCE") "±1%")
        (field (name "PART NUMBER") "R0402_30K_1%_0.0625W_100PPM")
        (field (name "POWER") "0.0625W")
        (field (name "AUTHOR") "CERN DEM JLC")
      )
      (libsource (lib "Resistors") (part "Resistor - 1%"))
    )
    (comp (ref "R207")
      (value "160k")
      (footprint "RESC1005X40N")
      (description "Resistor - 1%")
      (fields
        (field (name "TOLERANCE") "±1%")
        (field (name "PART NUMBER") "R0402_160K_1%_0.0625W_100PPM")
        (field (name "POWER") "0.0625W")
        (field (name "AUTHOR") "CERN DEM JLC")
      )
      (libsource (lib "Resistors") (part "Resistor - 1%"))
    )
    (comp (ref "R208")
      (value "75k")
      (footprint "RESC1005X40N")
      (description "Resistor - 1%")
      (fields
        (field (name "TOLERANCE") "±1%")
        (field (name "PART NUMBER") "R0402_75K_1%_0.0625W_100PPM")
        (field (name "POWER") "0.0625W")
        (field (name "AUTHOR") "CERN DEM JLC")
      )
      (libsource (lib "Resistors") (part "Resistor - 1%"))
    )
    (comp (ref "R209")
      (value "13k")
      (footprint "RESC1005X40N")
      (description "Resistor - 1%")
      (fields
        (field (name "TOLERANCE") "±1%")
        (field (name "PART NUMBER") "R0402_13K_1%_0.0625W_100PPM")
        (field (name "POWER") "0.0625W")
        (field (name "AUTHOR") "CERN DEM JLC")
      )
      (libsource (lib "Resistors") (part "Resistor - 1%"))
    )
    (comp (ref "R210")
      (value "15k")
      (footprint "RESC1005X40N")
      (description "Resistor - 1%")
      (fields
        (field (name "TOLERANCE") "±1%")
        (field (name "PART NUMBER") "R0402_15K_1%_0.0625W_100PPM")
        (field (name "POWER") "0.0625W")
        (field (name "AUTHOR") "CERN DEM JMW")
      )
      (libsource (lib "Resistors") (part "Resistor - 1%"))
    )
    (comp (ref "R217")
      (value "20k")
      (footprint "RESC1005X40N")
      (description "Resistor - 1%")
      (fields
        (field (name "TOLERANCE") "±1%")
        (field (name "PART NUMBER") "R0402_20K_1%_0.0625W_100PPM")
        (field (name "POWER") "0.0625W")
        (field (name "AUTHOR") "CERN DEM JLC")
      )
      (libsource (lib "Resistors") (part "Resistor - 1%"))
    )
    (comp (ref "R219")
      (value "3k9")
      (footprint "RESC1005X40N")
      (description "Resistor - 1%")
      (fields
        (field (name "TOLERANCE") "±1%")
        (field (name "PART NUMBER") "R0402_3K9_1%_0.0625W_100PPM")
        (field (name "POWER") "0.0625W")
        (field (name "AUTHOR") "CERN DEM JLC")
      )
      (libsource (lib "Resistors") (part "Resistor - 1%"))
    )
    (comp (ref "R223")
      (value "20k")
      (footprint "RESC1005X40N")
      (description "Resistor - 1%")
      (fields
        (field (name "TOLERANCE") "±1%")
        (field (name "PART NUMBER") "R0402_20K_1%_0.0625W_100PPM")
        (field (name "POWER") "0.0625W")
        (field (name "AUTHOR") "CERN DEM JLC")
      )
      (libsource (lib "Resistors") (part "Resistor - 1%"))
    )
    (comp (ref "R225")
      (value "3k9")
      (footprint "RESC1005X40N")
      (description "Resistor - 1%")
      (fields
        (field (name "TOLERANCE") "±1%")
        (field (name "PART NUMBER") "R0402_3K9_1%_0.0625W_100PPM")
        (field (name "POWER") "0.0625W")
        (field (name "AUTHOR") "CERN DEM JLC")
      )
      (libsource (lib "Resistors") (part "Resistor - 1%"))
    )
    (comp (ref "TP12")
      (value "Test Point")
      (footprint "TPS127")
      (fields (field (name "PART NUMBER") "SMD_PAD_1.27X1.27MM") (field (name "AUTHOR") "CERN DEM JLC"))
      (libsource (lib "Eletro-mechanical") (part "Test Point"))
    )
    (comp (ref "TP13")
      (value "Test Point")
      (footprint "TPS127")
      (fields (field (name "PART NUMBER") "SMD_PAD_1.27X1.27MM") (field (name "AUTHOR") "CERN DEM JLC"))
      (libsource (lib "Eletro-mechanical") (part "Test Point"))
    )
    (comp (ref "TP14")
      (value "Test Point")
      (footprint "TPS127")
      (fields (field (name "PART NUMBER") "SMD_PAD_1.27X1.27MM") (field (name "AUTHOR") "CERN DEM JLC"))
      (libsource (lib "Eletro-mechanical") (part "Test Point"))
    )
    (comp (ref "TP16")
      (value "Test Point")
      (footprint "TPS127")
      (fields (field (name "PART NUMBER") "SMD_PAD_1.27X1.27MM") (field (name "AUTHOR") "CERN DEM JLC"))
      (libsource (lib "Eletro-mechanical") (part "Test Point"))
    )
    (comp (ref "TP17")
      (value "Test Point")
      (footprint "TPS127")
      (fields (field (name "PART NUMBER") "SMD_PAD_1.27X1.27MM") (field (name "AUTHOR") "CERN DEM JLC"))
      (libsource (lib "Eletro-mechanical") (part "Test Point"))
    )
  )
  (nets
    (net (code "1") (name "/N8V0A") (class "Default")
      (node (ref "C231") (pin "2") (pinfunction "2_2") (pintype "passive"))
      (node (ref "C235") (pin "2") (pinfunction "2_2") (pintype "passive"))
      (node (ref "L206") (pin "2") (pinfunction "2_2") (pintype "passive"))
      (node (ref "L207") (pin "1") (pinfunction "1_1") (pintype "passive"))
    )
    (net (code "2") (name "/N8V0A1") (class "Default")
      (node (ref "C232") (pin "2") (pinfunction "2_2") (pintype "passive"))
      (node (ref "IC205") (pin "1") (pinfunction "IN_1") (pintype "input"))
      (node (ref "IC205") (pin "2") (pinfunction "IN_2") (pintype "input"))
      (node (ref "IC205") (pin "3") (pinfunction "~{SHDN}_3") (pintype "input"))
      (node (ref "IC205") (pin "9") (pinfunction "EP_9") (pintype "power_in"))
      (node (ref "L207") (pin "2") (pinfunction "2_2") (pintype "passive"))
    )
    (net (code "3") (name "/N8V0B") (class "Default")
      (node (ref "C46") (pin "2") (pinfunction "2_2") (pintype "passive"))
      (node (ref "C51") (pin "2") (pinfunction "2_2") (pintype "passive"))
      (node (ref "L11") (pin "2") (pinfunction "2_2") (pintype "passive"))
      (node (ref "L16") (pin "1") (pinfunction "1_1") (pintype "passive"))
    )
    (net (code "4") (name "/N8V0B1") (class "Default")
      (node (ref "C47") (pin "2") (pinfunction "2_2") (pintype "passive"))
      (node (ref "IC10") (pin "1") (pinfunction "IN_1") (pintype "input"))
      (node (ref "IC10") (pin "2") (pinfunction "IN_2") (pintype "input"))
      (node (ref "IC10") (pin "3") (pinfunction "~{SHDN}_3") (pintype "input"))
      (node (ref "IC10") (pin "9") (pinfunction "EP_9") (pintype "power_in"))
      (node (ref "L16") (pin "2") (pinfunction "2_2") (pintype "passive"))
    )
    (net (code "5") (name "/P8V0A") (class "Default")
      (node (ref "C228") (pin "1") (pinfunction "1_1") (pintype "passive"))
      (node (ref "C229") (pin "2") (pinfunction "2_2") (pintype "passive"))
      (node (ref "L204") (pin "2") (pinfunction "2_2") (pintype "passive"))
      (node (ref "L205") (pin "1") (pinfunction "1_1") (pintype "passive"))
    )
    (net (code "6") (name "/P8V0A1") (class "Default")
      (node (ref "C230") (pin "2") (pinfunction "2_2") (pintype "passive"))
      (node (ref "IC14") (pin "1") (pinfunction "~{SHDN}_1") (pintype "input"))
      (node (ref "IC14") (pin "2") (pinfunction "IN_2") (pintype "input"))
      (node (ref "L205") (pin "2") (pinfunction "2_2") (pintype "passive"))
    )
    (net (code "7") (name "/P8V0B") (class "Default")
      (node (ref "C42") (pin "1") (pinfunction "1_1") (pintype "passive"))
      (node (ref "C44") (pin "2") (pinfunction "2_2") (pintype "passive"))
      (node (ref "L10") (pin "1") (pinfunction "1_1") (pintype "passive"))
      (node (ref "L6") (pin "2") (pinfunction "2_2") (pintype "passive"))
    )
    (net (code "8") (name "/P8V0B1") (class "Default")
      (node (ref "C45") (pin "2") (pinfunction "2_2") (pintype "passive"))
      (node (ref "IC3") (pin "1") (pinfunction "~{SHDN}_1") (pintype "input"))
      (node (ref "IC3") (pin "2") (pinfunction "IN_2") (pintype "input"))
      (node (ref "L10") (pin "2") (pinfunction "2_2") (pintype "passive"))
    )
    (net (code "9") (name "/PGOOD") (class "Default")
      (node (ref "IC16") (pin "4") (pinfunction "PG_4") (pintype "output"))
      (node (ref "IC19") (pin "7") (pinfunction "PG_7") (pintype "output"))
      (node (ref "IC201") (pin "3") (pinfunction "~{RESE}T_3") (pintype "output"))
      (node (ref "IC202") (pin "4") (pinfunction "PGOOD_4") (pintype "output"))
    )
    (net (code "10") (name "/SCL") (class "Default")
      (node (ref "R125") (pin "1") (pinfunction "1_1") (pintype "passive"))
    )
    (net (code "11") (name "/SDA") (class "Default")
      (node (ref "R124") (pin "1") (pinfunction "1_1") (pintype "passive"))
    )
    (net (code "12") (name "GND") (class "Default")
      (node (ref "C117") (pin "2") (pinfunction "2_2") (pintype "passive"))
      (node (ref "C119") (pin "2") (pinfunction "2_2") (pintype "passive"))
      (node (ref "C120") (pin "2") (pinfunction "2_2") (pintype "passive"))
      (node (ref "C14") (pin "2") (pinfunction "2_2") (pintype "passive"))
      (node (ref "C146") (pin "2") (pinfunction "2_2") (pintype "passive"))
      (node (ref "C15") (pin "2") (pinfunction "2_2") (pintype "passive"))
      (node (ref "C152") (pin "1") (pinfunction "1_1") (pintype "passive"))
      (node (ref "C153") (pin "1") (pinfunction "1_1") (pintype "passive"))
      (node (ref "C154") (pin "1") (pinfunction "1_1") (pintype "passive"))
      (node (ref "C155") (pin "2") (pinfunction "2_2") (pintype "passive"))
      (node (ref "C156") (pin "2") (pinfunction "2_2") (pintype "passive"))
      (node (ref "C157") (pin "1") (pinfunction "1_1") (pintype "passive"))
      (node (ref "C158") (pin "1") (pinfunction "1_1") (pintype "passive"))
      (node (ref "C183") (pin "1") (pinfunction "1_1") (pintype "passive"))
      (node (ref "C208") (pin "1") (pinfunction "1_1") (pintype "passive"))
      (node (ref "C212") (pin "1") (pinfunction "1_1") (pintype "passive"))
      (node (ref "C213") (pin "1") (pinfunction "1_1") (pintype "passive"))
      (node (ref "C215") (pin "1") (pinfunction "1_1") (pintype "passive"))
      (node (ref "C216") (pin "1") (pinfunction "1_1") (pintype "passive"))
      (node (ref "C217") (pin "1") (pinfunction "1_1") (pintype "passive"))
      (node (ref "C218") (pin "1") (pinfunction "1_1") (pintype "passive"))
      (node (ref "C219") (pin "1") (pinfunction "1_1") (pintype "passive"))
      (node (ref "C220") (pin "1") (pinfunction "1_1") (pintype "passive"))
      (node (ref "C226") (pin "2") (pinfunction "2_2") (pintype "passive"))
      (node (ref "C228") (pin "2") (pinfunction "2_2") (pintype "passive"))
      (node (ref "C229") (pin "1") (pinfunction "1_1") (pintype "passive"))
      (node (ref "C230") (pin "1") (pinfunction "1_1") (pintype "passive"))
      (node (ref "C231") (pin "1") (pinfunction "1_1") (pintype "passive"))
      (node (ref "C232") (pin "1") (pinfunction "1_1") (pintype "passive"))
      (node (ref "C233") (pin "1") (pinfunction "1_1") (pintype "passive"))
      (node (ref "C234") (pin "1") (pinfunction "1_1") (pintype "passive"))
      (node (ref "C235") (pin "1") (pinfunction "1_1") (pintype "passive"))
      (node (ref "C37") (pin "2") (pinfunction "2_2") (pintype "passive"))
      (node (ref "C38") (pin "2") (pinfunction "2_2") (pintype "passive"))
      (node (ref "C42") (pin "2") (pinfunction "2_2") (pintype "passive"))
      (node (ref "C43") (pin "2") (pinfunction "2_2") (pintype "passive"))
      (node (ref "C44") (pin "1") (pinfunction "1_1") (pintype "passive"))
      (node (ref "C45") (pin "1") (pinfunction "1_1") (pintype "passive"))
      (node (ref "C46") (pin "1") (pinfunction "1_1") (pintype "passive"))
      (node (ref "C47") (pin "1") (pinfunction "1_1") (pintype "passive"))
      (node (ref "C48") (pin "1") (pinfunction "1_1") (pintype "passive"))
      (node (ref "C49") (pin "1") (pinfunction "1_1") (pintype "passive"))
      (node (ref "C50") (pin "1") (pinfunction "1_1") (pintype "passive"))
      (node (ref "C51") (pin "1") (pinfunction "1_1") (pintype "passive"))
      (node (ref "C79") (pin "1") (pinfunction "1_1") (pintype "passive"))
      (node (ref "D2") (pin "2") (pinfunction "A_2") (pintype "passive"))
      (node (ref "D200") (pin "2") (pinfunction "A_2") (pintype "passive"))
      (node (ref "D201") (pin "1") (pinfunction "C_1") (pintype "passive"))
      (node (ref "D3") (pin "1") (pinfunction "C_1") (pintype "passive"))
      (node (ref "D6") (pin "2") (pinfunction "A_2") (pintype "passive"))
      (node (ref "IC10") (pin "4") (pinfunction "GND_4") (pintype "power_in"))
      (node (ref "IC10") (pin "5") (pinfunction "GND_5") (pintype "power_in"))
      (node (ref "IC12") (pin "4") (pinfunction "GND_4") (pintype "power_in"))
      (node (ref "IC14") (pin "3") (pinfunction "GND_3") (pintype "power_in"))
      (node (ref "IC14") (pin "6") (pinfunction "GND_6") (pintype "power_in"))
      (node (ref "IC16") (pin "11") (pinfunction "GND_11") (pintype "power_in"))
      (node (ref "IC16") (pin "5") (pinfunction "ILIM_5") (pintype "input"))
      (node (ref "IC16") (pin "8") (pinfunction "GND_8") (pintype "power_in"))
      (node (ref "IC19") (pin "11") (pinfunction "FSEL_11") (pintype "input"))
      (node (ref "IC19") (pin "3") (pinfunction "GND_3") (pintype "power_in"))
      (node (ref "IC19") (pin "4") (pinfunction "AGND_4") (pintype "power_in"))
      (node (ref "IC201") (pin "9") (pinfunction "GND_9") (pintype "power_in"))
      (node (ref "IC202") (pin "8") (pinfunction "GND_8") (pintype "power_in"))
      (node (ref "IC202") (pin "9") (pinfunction "GND_9") (pintype "power_in"))
      (node (ref "IC205") (pin "4") (pinfunction "GND_4") (pintype "power_in"))
      (node (ref "IC205") (pin "5") (pinfunction "GND_5") (pintype "power_in"))
      (node (ref "IC3") (pin "3") (pinfunction "GND_3") (pintype "power_in"))
      (node (ref "IC3") (pin "6") (pinfunction "GND_6") (pintype "power_in"))
      (node (ref "J18") (pin "1") (pinfunction "1_1") (pintype "bidirectional"))
      (node (ref "J18") (pin "2") (pinfunction "2_2") (pintype "bidirectional"))
      (node (ref "L201") (pin "2") (pinfunction "2_2") (pintype "passive"))
      (node (ref "LD1") (pin "2") (pinfunction "A_2") (pintype "passive"))
      (node (ref "LD10") (pin "1") (pinfunction "C_1") (pintype "passive"))
      (node (ref "LD11") (pin "1") (pinfunction "C_1") (pintype "passive"))
      (node (ref "LD3") (pin "1") (pinfunction "C_1") (pintype "passive"))
      (node (ref "LD4") (pin "1") (pinfunction "C_1") (pintype "passive"))
      (node (ref "LD7") (pin "1") (pinfunction "C_1") (pintype "passive"))
      (node (ref "R104") (pin "1") (pinfunction "1_1") (pintype "passive"))
      (node (ref "R106") (pin "1") (pinfunction "1_1") (pintype "passive"))
      (node (ref "R126") (pin "1") (pinfunction "1_1") (pintype "passive"))
      (node (ref "R127") (pin "1") (pinfunction "1_1") (pintype "passive"))
      (node (ref "R128") (pin "1") (pinfunction "1_1") (pintype "passive"))
      (node (ref "R136") (pin "1") (pinfunction "1_1") (pintype "passive"))
      (node (ref "R205") (pin "2") (pinfunction "2_2") (pintype "passive"))
      (node (ref "R209") (pin "1") (pinfunction "1_1") (pintype "passive"))
      (node (ref "R210") (pin "1") (pinfunction "1_1") (pintype "passive"))
      (node (ref "R219") (pin "1") (pinfunction "1_1") (pintype "passive"))
      (node (ref "R225") (pin "1") (pinfunction "1_1") (pintype "passive"))
      (node (ref "R90") (pin "1") (pinfunction "1_1") (pintype "passive"))
      (node (ref "R93") (pin "1") (pinfunction "1_1") (pintype "passive"))
    )
    (net (code "13") (name "N2V5A") (class "Default")
      (node (ref "C49") (pin "2") (pinfunction "2_2") (pintype "passive"))
      (node (ref "C50") (pin "2") (pinfunction "2_2") (pintype "passive"))
      (node (ref "D3") (pin "2") (pinfunction "A_2") (pintype "passive"))
      (node (ref "IC10") (pin "7") (pinfunction "OUT_7") (pintype "power_in"))
      (node (ref "IC10") (pin "8") (pinfunction "OUT_8") (pintype "power_in"))
      (node (ref "R91") (pin "2") (pinfunction "2_2") (pintype "passive"))
    )
    (net (code "14") (name "N7V5A") (class "Default")
      (node (ref "C233") (pin "2") (pinfunction "2_2") (pintype "passive"))
      (node (ref "C234") (pin "2") (pinfunction "2_2") (pintype "passive"))
      (node (ref "D201") (pin "2") (pinfunction "A_2") (pintype "passive"))
      (node (ref "IC205") (pin "7") (pinfunction "OUT_7") (pintype "power_in"))
      (node (ref "IC205") (pin "8") (pinfunction "OUT_8") (pintype "power_in"))
      (node (ref "R223") (pin "2") (pinfunction "2_2") (pintype "passive"))
      (node (ref "R94") (pin "1") (pinfunction "1_1") (pintype "passive"))
      (node (ref "TP12") (pin "1") (pinfunction "1_1") (pintype "bidirectional"))
    )
    (net (code "15") (name "N8V0") (class "Default")
      (node (ref "C209") (pin "1") (pinfunction "1_1") (pintype "passive"))
      (node (ref "C210") (pin "1") (pinfunction "1_1") (pintype "passive"))
      (node (ref "C211") (pin "1") (pinfunction "1_1") (pintype "passive"))
      (node (ref "C218") (pin "2") (pinfunction "2_2") (pintype "passive"))
      (node (ref "C219") (pin "2") (pinfunction "2_2") (pintype "passive"))
      (node (ref "IC201") (pin "12") (pinfunction "OUT_12") (pintype "output"))
      (node (ref "IC201") (pin "13") (pinfunction "SOUT_13") (pintype "output"))
      (node (ref "IC201") (pin "8") (pinfunction "SOUT_8") (pintype "output"))
      (node (ref "L11") (pin "1") (pinfunction "1_1") (pintype "passive"))
      (node (ref "L206") (pin "1") (pinfunction "1_1") (pintype "passive"))
      (node (ref "R204") (pin "1") (pinfunction "1_1") (pintype "passive"))
      (node (ref "R206") (pin "1") (pinfunction "1_1") (pintype "passive"))
    )
    (net (code "16") (name "Net-(F1-Pad1)") (class "Default")
      (node (ref "F1") (pin "1") (pinfunction "1_1") (pintype "passive"))
      (node (ref "J18") (pin "3") (pinfunction "3_3") (pintype "bidirectional"))
      (node (ref "J18") (pin "4") (pinfunction "4_4") (pintype "bidirectional"))
    )
    (net (code "17") (name "Net-(IC3-ADJ)") (class "Default")
      (node (ref "IC3") (pin "5") (pinfunction "ADJ_5") (pintype "input"))
      (node (ref "R82") (pin "1") (pinfunction "1_1") (pintype "passive"))
      (node (ref "R90") (pin "2") (pinfunction "2_2") (pintype "passive"))
    )
    (net (code "18") (name "Net-(IC10-ADJ)") (class "Default")
      (node (ref "IC10") (pin "6") (pinfunction "ADJ_6") (pintype "input"))
      (node (ref "R92") (pin "1") (pinfunction "1_1") (pintype "passive"))
      (node (ref "R93") (pin "2") (pinfunction "2_2") (pintype "passive"))
    )
    (net (code "19") (name "Net-(IC12-A0)") (class "Default")
      (node (ref "IC12") (pin "7") (pinfunction "A0_7") (pintype "input"))
      (node (ref "R128") (pin "2") (pinfunction "2_2") (pintype "passive"))
    )
    (net (code "20") (name "Net-(IC12-A1)") (class "Default")
      (node (ref "IC12") (pin "6") (pinfunction "A1_6") (pintype "input"))
      (node (ref "R127") (pin "2") (pinfunction "2_2") (pintype "passive"))
    )
    (net (code "21") (name "Net-(IC12-A2)") (class "Default")
      (node (ref "IC12") (pin "5") (pinfunction "A2_5") (pintype "input"))
      (node (ref "R126") (pin "2") (pinfunction "2_2") (pintype "passive"))
    )
    (net (code "22") (name "Net-(IC12-O.S.)") (class "Default")
      (node (ref "IC12") (pin "3") (pinfunction "O.S._3") (pintype "output"))
      (node (ref "LD7") (pin "3") (pinfunction "C_3") (pintype "passive"))
      (node (ref "R123") (pin "1") (pinfunction "1_1") (pintype "passive"))
    )
    (net (code "23") (name "Net-(IC12-SCL)") (class "Default")
      (node (ref "IC12") (pin "2") (pinfunction "SCL_2") (pintype "input"))
      (node (ref "R122") (pin "1") (pinfunction "1_1") (pintype "passive"))
      (node (ref "R125") (pin "2") (pinfunction "2_2") (pintype "passive"))
    )
    (net (code "24") (name "Net-(IC12-SDA)") (class "Default")
      (node (ref "IC12") (pin "1") (pinfunction "SDA_1") (pintype "bidirectional"))
      (node (ref "R121") (pin "1") (pinfunction "1_1") (pintype "passive"))
      (node (ref "R124") (pin "2") (pinfunction "2_2") (pintype "passive"))
    )
    (net (code "25") (name "Net-(IC14-ADJ)") (class "Default")
      (node (ref "IC14") (pin "5") (pinfunction "ADJ_5") (pintype "input"))
      (node (ref "R217") (pin "1") (pinfunction "1_1") (pintype "passive"))
      (node (ref "R219") (pin "2") (pinfunction "2_2") (pintype "passive"))
    )
    (net (code "26") (name "Net-(IC16-PGFB)") (class "Default")
      (node (ref "IC16") (pin "6") (pinfunction "PGFB_6") (pintype "input"))
      (node (ref "R106") (pin "2") (pinfunction "2_2") (pintype "passive"))
      (node (ref "R110") (pin "1") (pinfunction "1_1") (pintype "passive"))
    )
    (net (code "27") (name "Net-(IC16-SET)") (class "Default")
      (node (ref "C146") (pin "1") (pinfunction "1_1") (pintype "passive"))
      (node (ref "IC16") (pin "7") (pinfunction "SET_7") (pintype "input"))
      (node (ref "R104") (pin "2") (pinfunction "2_2") (pintype "passive"))
    )
    (net (code "28") (name "Net-(IC19-FB)") (class "Default")
      (node (ref "IC19") (pin "5") (pinfunction "FB_5") (pintype "input"))
      (node (ref "R135") (pin "1") (pinfunction "1_1") (pintype "passive"))
      (node (ref "R136") (pin "2") (pinfunction "2_2") (pintype "passive"))
    )
    (net (code "29") (name "Net-(IC19-MODE)") (class "Default")
      (node (ref "IC19") (pin "10") (pinfunction "MODE_10") (pintype "input"))
      (node (ref "R134") (pin "1") (pinfunction "1_1") (pintype "passive"))
    )
    (net (code "30") (name "Net-(IC19-SS{slash}TR)") (class "Default")
      (node (ref "C38") (pin "1") (pinfunction "1_1") (pintype "passive"))
      (node (ref "IC19") (pin "9") (pinfunction "SS/TR_9") (pintype "input"))
    )
    (net (code "31") (name "Net-(IC19-SW)") (class "Default")
      (node (ref "IC19") (pin "2") (pinfunction "SW_2") (pintype "output"))
      (node (ref "L4") (pin "1") (pinfunction "1_1") (pintype "passive"))
    )
    (net (code "32") (name "Net-(IC201-BST)") (class "Default")
      (node (ref "C206") (pin "2") (pinfunction "2_2") (pintype "passive"))
      (node (ref "IC201") (pin "10") (pinfunction "BST_10") (pintype "output"))
    )
    (net (code "33") (name "Net-(IC201-EN{slash}UVLO)") (class "Default")
      (node (ref "IC201") (pin "2") (pinfunction "EN/UVLO_2") (pintype "input"))
      (node (ref "R89") (pin "2") (pinfunction "2_2") (pintype "passive"))
    )
    (net (code "34") (name "Net-(IC201-FB)") (class "Default")
      (node (ref "IC201") (pin "7") (pinfunction "FB_7") (pintype "input"))
      (node (ref "R205") (pin "1") (pinfunction "1_1") (pintype "passive"))
      (node (ref "R206") (pin "2") (pinfunction "2_2") (pintype "passive"))
    )
    (net (code "35") (name "Net-(IC201-LX)") (class "Default")
      (node (ref "C206") (pin "1") (pinfunction "1_1") (pintype "passive"))
      (node (ref "IC201") (pin "11") (pinfunction "LX_11") (pintype "output"))
      (node (ref "L201") (pin "1") (pinfunction "1_1") (pintype "passive"))
    )
    (net (code "36") (name "Net-(IC201-RT{slash}SYNC)") (class "Default")
      (node (ref "IC201") (pin "6") (pinfunction "RT/SYNC_6") (pintype "input"))
      (node (ref "R204") (pin "2") (pinfunction "2_2") (pintype "passive"))
    )
    (net (code "37") (name "Net-(IC201-SS)") (class "Default")
      (node (ref "C210") (pin "2") (pinfunction "2_2") (pintype "passive"))
      (node (ref "C211") (pin "2") (pinfunction "2_2") (pintype "passive"))
      (node (ref "IC201") (pin "4") (pinfunction "SS_4") (pintype "input"))
    )
    (net (code "38") (name "Net-(IC201-VCC)") (class "Default")
      (node (ref "C209") (pin "2") (pinfunction "2_2") (pintype "passive"))
      (node (ref "IC201") (pin "5") (pinfunction "VCC_5") (pintype "output"))
    )
    (net (code "39") (name "Net-(IC202-FB)") (class "Default")
      (node (ref "C214") (pin "1") (pinfunction "1_1") (pintype "passive"))
      (node (ref "IC202") (pin "5") (pinfunction "FB_5") (pintype "input"))
      (node (ref "R207") (pin "1") (pinfunction "1_1") (pintype "passive"))
      (node (ref "R209") (pin "2") (pinfunction "2_2") (pintype "passive"))
    )
    (net (code "40") (name "Net-(IC202-INTVCC)") (class "Default")
      (node (ref "C220") (pin "2") (pinfunction "2_2") (pintype "passive"))
      (node (ref "IC202") (pin "6") (pinfunction "INTVCC_6") (pintype "output"))
    )
    (net (code "41") (name "Net-(IC202-MODE{slash}SYNC)") (class "Default")
      (node (ref "IC202") (pin "7") (pinfunction "MODE/SYNC_7") (pintype "input"))
      (node (ref "R208") (pin "1") (pinfunction "1_1") (pintype "passive"))
      (node (ref "R210") (pin "2") (pinfunction "2_2") (pintype "passive"))
    )
    (net (code "42") (name "Net-(IC202-RUN)") (class "Default")
      (node (ref "IC202") (pin "3") (pinfunction "RUN_3") (pintype "input"))
      (node (ref "R88") (pin "2") (pinfunction "2_2") (pintype "passive"))
    )
    (net (code "43") (name "Net-(IC202-SW)") (class "Default")
      (node (ref "IC202") (pin "1") (pinfunction "SW_1") (pintype "output"))
      (node (ref "L202") (pin "1") (pinfunction "1_1") (pintype "passive"))
    )
    (net (code "44") (name "Net-(IC205-ADJ)") (class "Default")
      (node (ref "IC205") (pin "6") (pinfunction "ADJ_6") (pintype "input"))
      (node (ref "R223") (pin "1") (pinfunction "1_1") (pintype "passive"))
      (node (ref "R225") (pin "2") (pinfunction "2_2") (pintype "passive"))
    )
    (net (code "45") (name "Net-(LD1-C)") (class "Default")
      (node (ref "LD1") (pin "1") (pinfunction "C_1") (pintype "passive"))
      (node (ref "R94") (pin "2") (pinfunction "2_2") (pintype "passive"))
    )
    (net (code "46") (name "Net-(LD3-A)") (class "Default")
      (node (ref "LD3") (pin "2") (pinfunction "A_2") (pintype "passive"))
      (node (ref "R33") (pin "2") (pinfunction "2_2") (pintype "passive"))
    )
    (net (code "47") (name "Net-(LD4-A)") (class "Default")
      (node (ref "LD4") (pin "2") (pinfunction "A_2") (pintype "passive"))
      (node (ref "R115") (pin "2") (pinfunction "2_2") (pintype "passive"))
    )
    (net (code "48") (name "Net-(LD7A-A)") (class "Default")
      (node (ref "LD7") (pin "2") (pinfunction "A_2") (pintype "passive"))
      (node (ref "R97") (pin "2") (pinfunction "2_2") (pintype "passive"))
    )
    (net (code "49") (name "Net-(LD7B-A)") (class "Default")
      (node (ref "LD7") (pin "4") (pinfunction "A_4") (pintype "passive"))
      (node (ref "R143") (pin "2") (pinfunction "2_2") (pintype "passive"))
    )
    (net (code "50") (name "Net-(LD10-A)") (class "Default")
      (node (ref "LD10") (pin "2") (pinfunction "A_2") (pintype "passive"))
      (node (ref "R116") (pin "2") (pinfunction "2_2") (pintype "passive"))
    )
    (net (code "51") (name "Net-(LD11-A)") (class "Default")
      (node (ref "LD11") (pin "2") (pinfunction "A_2") (pintype "passive"))
      (node (ref "R144") (pin "2") (pinfunction "2_2") (pintype "passive"))
    )
    (net (code "52") (name "Net-(R41-Pad1)") (class "Default")
      (node (ref "R41") (pin "1") (pinfunction "1_1") (pintype "passive"))
      (node (ref "R82") (pin "2") (pinfunction "2_2") (pintype "passive"))
    )
    (net (code "53") (name "Net-(R91-Pad1)") (class "Default")
      (node (ref "R91") (pin "1") (pinfunction "1_1") (pintype "passive"))
      (node (ref "R92") (pin "2") (pinfunction "2_2") (pintype "passive"))
    )
    (net (code "54") (name "Net-(R120-Pad1)") (class "Default")
      (node (ref "R120") (pin "1") (pinfunction "1_1") (pintype "passive"))
      (node (ref "R123") (pin "2") (pinfunction "2_2") (pintype "passive"))
    )
    (net (code "55") (name "P2V5A") (class "Default")
      (node (ref "C14") (pin "1") (pinfunction "1_1") (pintype "passive"))
      (node (ref "C15") (pin "1") (pinfunction "1_1") (pintype "passive"))
      (node (ref "C43") (pin "1") (pinfunction "1_1") (pintype "passive"))
      (node (ref "D2") (pin "1") (pinfunction "C_1") (pintype "passive"))
      (node (ref "IC3") (pin "4") (pinfunction "OUT_4") (pintype "power_in"))
      (node (ref "R41") (pin "2") (pinfunction "2_2") (pintype "passive"))
    )
    (net (code "56") (name "P3V3_MP") (class "Default")
      (node (ref "C48") (pin "2") (pinfunction "2_2") (pintype "passive"))
      (node (ref "IC12") (pin "8") (pinfunction "+VS_8") (pintype "power_in"))
      (node (ref "R116") (pin "1") (pinfunction "1_1") (pintype "passive"))
      (node (ref "R120") (pin "2") (pinfunction "2_2") (pintype "passive"))
      (node (ref "R121") (pin "2") (pinfunction "2_2") (pintype "passive"))
      (node (ref "R122") (pin "2") (pinfunction "2_2") (pintype "passive"))
      (node (ref "R143") (pin "1") (pinfunction "1_1") (pintype "passive"))
      (node (ref "TP17") (pin "1") (pinfunction "1_1") (pintype "bidirectional"))
    )
    (net (code "57") (name "P5V5") (class "Default")
      (node (ref "C152") (pin "2") (pinfunction "2_2") (pintype "passive"))
      (node (ref "C153") (pin "2") (pinfunction "2_2") (pintype "passive"))
      (node (ref "C154") (pin "2") (pinfunction "2_2") (pintype "passive"))
      (node (ref "IC19") (pin "6") (pinfunction "VOS_6") (pintype "input"))
      (node (ref "L4") (pin "2") (pinfunction "2_2") (pintype "passive"))
      (node (ref "L5") (pin "1") (pinfunction "1_1") (pintype "passive"))
      (node (ref "R135") (pin "2") (pinfunction "2_2") (pintype "passive"))
    )
    (net (code "58") (name "P5V5A") (class "Default")
      (node (ref "C117") (pin "1") (pinfunction "1_1") (pintype "passive"))
      (node (ref "C156") (pin "1") (pinfunction "1_1") (pintype "passive"))
      (node (ref "C183") (pin "2") (pinfunction "2_2") (pintype "passive"))
      (node (ref "IC16") (pin "1") (pinfunction "IN_1") (pintype "input"))
      (node (ref "IC16") (pin "2") (pinfunction "IN_2") (pintype "input"))
      (node (ref "IC16") (pin "3") (pinfunction "EN/UV_3") (pintype "input"))
      (node (ref "L5") (pin "2") (pinfunction "2_2") (pintype "passive"))
    )
    (net (code "59") (name "P7V5A") (class "Default")
      (node (ref "C155") (pin "1") (pinfunction "1_1") (pintype "passive"))
      (node (ref "C226") (pin "1") (pinfunction "1_1") (pintype "passive"))
      (node (ref "C37") (pin "1") (pinfunction "1_1") (pintype "passive"))
      (node (ref "D200") (pin "1") (pinfunction "C_1") (pintype "passive"))
      (node (ref "IC14") (pin "4") (pinfunction "OUT_4") (pintype "power_in"))
      (node (ref "R115") (pin "1") (pinfunction "1_1") (pintype "passive"))
      (node (ref "R217") (pin "2") (pinfunction "2_2") (pintype "passive"))
      (node (ref "TP16") (pin "1") (pinfunction "1_1") (pintype "bidirectional"))
    )
    (net (code "60") (name "P8V0") (class "Default")
      (node (ref "C214") (pin "2") (pinfunction "2_2") (pintype "passive"))
      (node (ref "C215") (pin "2") (pinfunction "2_2") (pintype "passive"))
      (node (ref "C216") (pin "2") (pinfunction "2_2") (pintype "passive"))
      (node (ref "C217") (pin "2") (pinfunction "2_2") (pintype "passive"))
      (node (ref "L202") (pin "2") (pinfunction "2_2") (pintype "passive"))
      (node (ref "L204") (pin "1") (pinfunction "1_1") (pintype "passive"))
      (node (ref "L6") (pin "1") (pinfunction "1_1") (pintype "passive"))
      (node (ref "R207") (pin "2") (pinfunction "2_2") (pintype "passive"))
    )
    (net (code "61") (name "P12V0") (class "Default")
      (node (ref "C157") (pin "2") (pinfunction "2_2") (pintype "passive"))
      (node (ref "C158") (pin "2") (pinfunction "2_2") (pintype "passive"))
      (node (ref "C208") (pin "2") (pinfunction "2_2") (pintype "passive"))
      (node (ref "C212") (pin "2") (pinfunction "2_2") (pintype "passive"))
      (node (ref "C213") (pin "2") (pinfunction "2_2") (pintype "passive"))
      (node (ref "D6") (pin "1") (pinfunction "C_1") (pintype "passive"))
      (node (ref "F1") (pin "2") (pinfunction "2_2") (pintype "passive"))
      (node (ref "IC19") (pin "1") (pinfunction "VIN_1") (pintype "input"))
      (node (ref "IC19") (pin "8") (pinfunction "EN_8") (pintype "input"))
      (node (ref "IC201") (pin "1") (pinfunction "IN_1") (pintype "power_in"))
      (node (ref "IC202") (pin "2") (pinfunction "VIN_2") (pintype "input"))
      (node (ref "R134") (pin "2") (pinfunction "2_2") (pintype "passive"))
      (node (ref "R208") (pin "2") (pinfunction "2_2") (pintype "passive"))
      (node (ref "R33") (pin "1") (pinfunction "1_1") (pintype "passive"))
      (node (ref "R88") (pin "1") (pinfunction "1_1") (pintype "passive"))
      (node (ref "R89") (pin "1") (pinfunction "1_1") (pintype "passive"))
      (node (ref "TP14") (pin "1") (pinfunction "1_1") (pintype "bidirectional"))
    )
    (net (code "62") (name "VDD") (class "Default")
      (node (ref "C119") (pin "1") (pinfunction "1_1") (pintype "passive"))
      (node (ref "C120") (pin "1") (pinfunction "1_1") (pintype "passive"))
      (node (ref "C79") (pin "2") (pinfunction "2_2") (pintype "passive"))
      (node (ref "IC16") (pin "10") (pinfunction "OUT_10") (pintype "output"))
      (node (ref "IC16") (pin "9") (pinfunction "OUTS_9") (pintype "output"))
      (node (ref "R110") (pin "2") (pinfunction "2_2") (pintype "passive"))
      (node (ref "R144") (pin "1") (pinfunction "1_1") (pintype "passive"))
      (node (ref "R97") (pin "1") (pinfunction "1_1") (pintype "passive"))
      (node (ref "TP13") (pin "1") (pinfunction "1_1") (pintype "bidirectional"))
    )
  )
)
